# 2015-02-06_01-57-191.net
KiCad netlist of a schematic drawn in Altium Designer
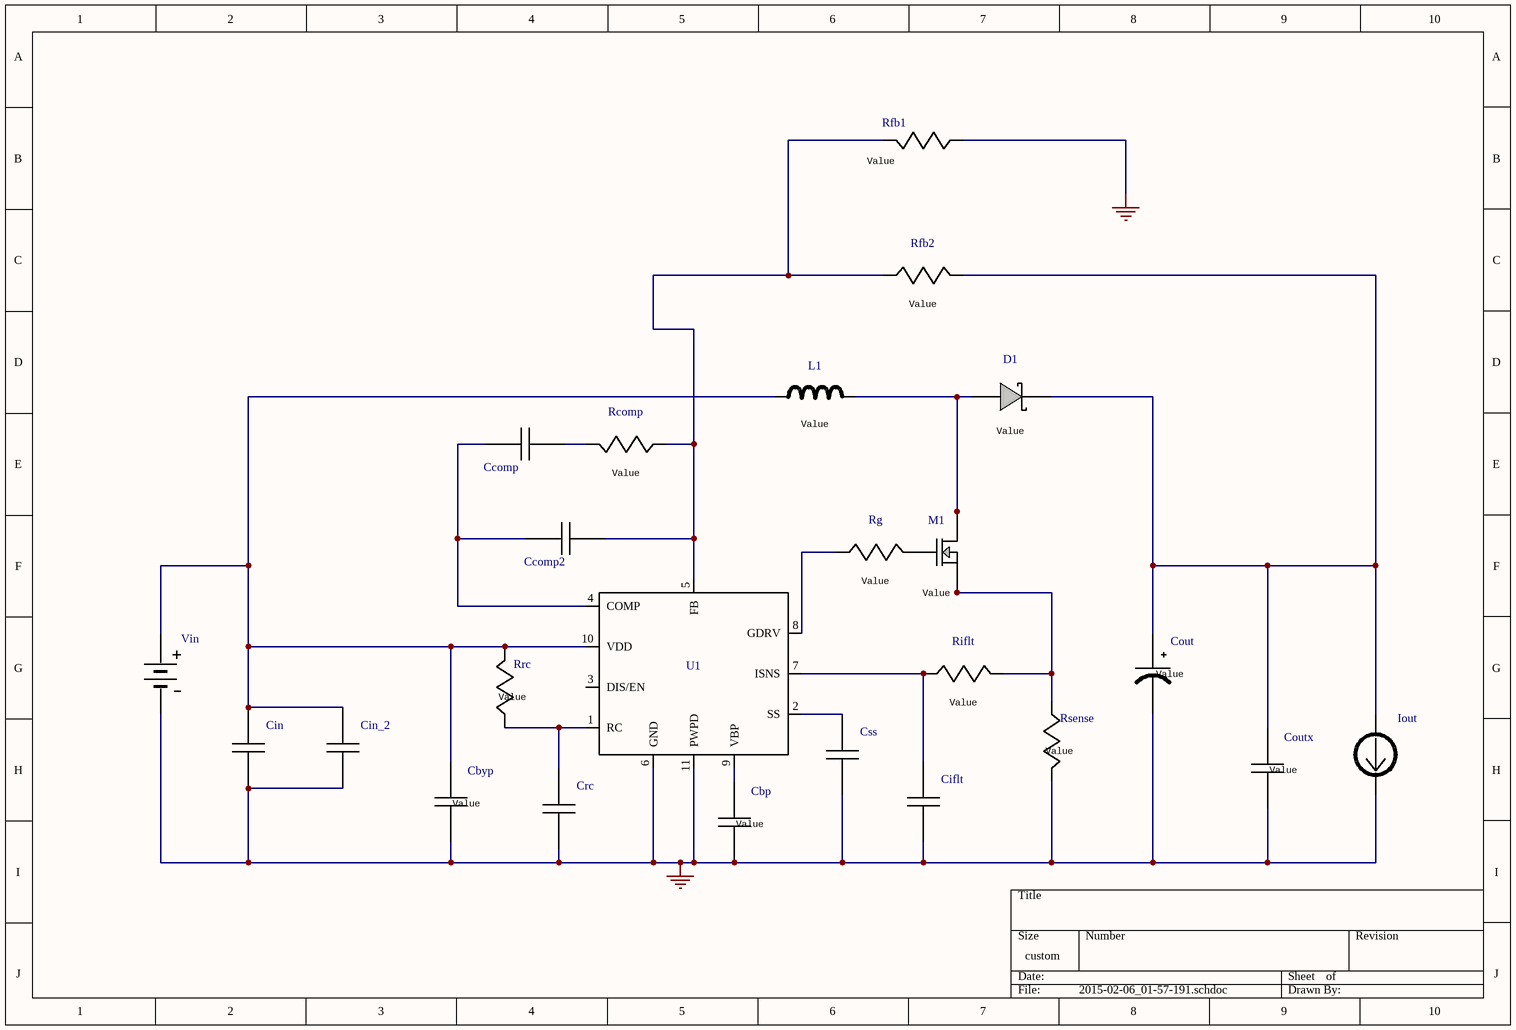
[diagram p0: 2015-02-06_01-57-191.schdoc]

(export (version "E")
  (design (tool "Eeschema 10.0.6"))
  (components
    (comp (ref "Cbp")
      (value "Value")
      (footprint "1608")
      (description "Imported")
      (fields (field (name "MANUFACTURER_PART_NUMBER") "C1608X5R1C105K"))
      (libsource (lib "TI WEBENCH") (part "C1608X5R1C105K"))
    )
    (comp (ref "Cbyp")
      (value "Value")
      (footprint "0805")
      (description "Imported")
      (fields (field (name "MANUFACTURER_PART_NUMBER") "EMK212B7474KD-T"))
      (libsource (lib "TI WEBENCH") (part "EMK212B7474KD-T"))
    )
    (comp (ref "Ccomp")
      (value "CC0805KRX7R9BB27")
      (footprint "0805")
      (description "Imported")
      (fields (field (name "MANUFACTURER_PART_NUMBER") "CC0805KRX7R9BB272"))
      (libsource (lib "TI WEBENCH") (part "CC0805KRX7R9BB27"))
    )
    (comp (ref "Ccomp2")
      (value "CC0805JRNPO9BN10")
      (footprint "0805")
      (description "Imported")
      (fields (field (name "MANUFACTURER_PART_NUMBER") "CC0805JRNPO9BN101"))
      (libsource (lib "TI WEBENCH") (part "CC0805JRNPO9BN10"))
    )
    (comp (ref "Ciflt")
      (value "CC0805JRNPO9BN15")
      (footprint "0805")
      (description "Imported")
      (fields (field (name "MANUFACTURER_PART_NUMBER") "CC0805JRNPO9BN151"))
      (libsource (lib "TI WEBENCH") (part "CC0805JRNPO9BN15"))
    )
    (comp (ref "Cin")
      (value "GRM21BR61E475MA1")
      (footprint "0805")
      (description "Imported")
      (fields (field (name "MANUFACTURER_PART_NUMBER") "GRM21BR61E475MA12L"))
      (libsource (lib "TI WEBENCH") (part "GRM21BR61E475MA1"))
    )
    (comp (ref "Cin_2")
      (value "GRM21BR61E475MA1")
      (footprint "0805")
      (description "Imported")
      (fields (field (name "MANUFACTURER_PART_NUMBER") "GRM21BR61E475MA12L"))
      (libsource (lib "TI WEBENCH") (part "GRM21BR61E475MA1"))
    )
    (comp (ref "Cout")
      (value "Value")
      (footprint "CAPSMT_62_E12")
      (description "Imported")
      (fields (field (name "MANUFACTURER_PART_NUMBER") "35SVPF82M"))
      (libsource (lib "TI WEBENCH") (part "35SVPF82M"))
    )
    (comp (ref "Coutx")
      (value "Value")
      (footprint "0805")
      (description "Imported")
      (fields (field (name "MANUFACTURER_PART_NUMBER") "GMK212B7105KG-T"))
      (libsource (lib "TI WEBENCH") (part "GMK212B7105KG-T"))
    )
    (comp (ref "Crc")
      (value "CC0805JRNPO9BN10")
      (footprint "0805")
      (description "Imported")
      (fields (field (name "MANUFACTURER_PART_NUMBER") "CC0805JRNPO9BN101"))
      (libsource (lib "TI WEBENCH") (part "CC0805JRNPO9BN10"))
    )
    (comp (ref "Css")
      (value "GRM155R61A683KA0")
      (footprint "0402")
      (description "Imported")
      (fields (field (name "MANUFACTURER_PART_NUMBER") "GRM155R61A683KA01D"))
      (libsource (lib "TI WEBENCH") (part "GRM155R61A683KA0"))
    )
    (comp (ref "D1")
      (value "Value")
      (footprint "SMA")
      (description "Imported")
      (fields (field (name "MANUFACTURER_PART_NUMBER") "B240A-13-F"))
      (libsource (lib "TI WEBENCH") (part "B240A-13-F"))
    )
    (comp (ref "Iout")
      (value "WB_CURRENT_LOAD")
      (description "Imported")
      (libsource (lib "TI WEBENCH") (part "WB_CURRENT_LOAD"))
    )
    (comp (ref "L1")
      (value "Value")
      (footprint "SRR1210")
      (description "Imported")
      (fields (field (name "MANUFACTURER_PART_NUMBER") "SRR1210-220M"))
      (libsource (lib "TI WEBENCH") (part "SRR1210-220M"))
    )
    (comp (ref "M1")
      (value "Value")
      (footprint "TRANS_NexFET_Q5A")
      (description "Imported")
      (fields (field (name "MANUFACTURER_PART_NUMBER") "CSD17551Q5A"))
      (libsource (lib "TI WEBENCH") (part "CSD17551Q5A"))
    )
    (comp (ref "Rcomp")
      (value "Value")
      (footprint "0402")
      (description "Imported")
      (fields (field (name "MANUFACTURER_PART_NUMBER") "CRCW040256K2FKED"))
      (libsource (lib "TI WEBENCH") (part "CRCW040256K2FKED"))
    )
    (comp (ref "Rfb1")
      (value "Value")
      (footprint "0402")
      (description "Imported")
      (fields (field (name "MANUFACTURER_PART_NUMBER") "CRCW04021K40FKED"))
      (libsource (lib "TI WEBENCH") (part "CRCW04021K40FKED"))
    )
    (comp (ref "Rfb2")
      (value "Value")
      (footprint "0805")
      (description "Imported")
      (fields (field (name "MANUFACTURER_PART_NUMBER") "RR1220P-473-D"))
      (libsource (lib "TI WEBENCH") (part "RR1220P-473-D"))
    )
    (comp (ref "Rg")
      (value "Value")
      (footprint "0402")
      (description "Imported")
      (fields (field (name "MANUFACTURER_PART_NUMBER") "CRCW040217R8FKED"))
      (libsource (lib "TI WEBENCH") (part "CRCW040217R8FKED"))
    )
    (comp (ref "Riflt")
      (value "Value")
      (footprint "0402")
      (description "Imported")
      (fields (field (name "MANUFACTURER_PART_NUMBER") "CRCW04021K00FKED"))
      (libsource (lib "TI WEBENCH") (part "CRCW04021K00FKED"))
    )
    (comp (ref "Rrc")
      (value "Value")
      (footprint "0402")
      (description "Imported")
      (fields (field (name "MANUFACTURER_PART_NUMBER") "CRCW0402316KFKED"))
      (libsource (lib "TI WEBENCH") (part "CRCW0402316KFKED"))
    )
    (comp (ref "Rsense")
      (value "Value")
      (footprint "1206")
      (description "Imported")
      (fields (field (name "MANUFACTURER_PART_NUMBER") "CSR1206FK25L0"))
      (libsource (lib "TI WEBENCH") (part "CSR1206FK25L0"))
    )
    (comp (ref "U1")
      (value "TPS40210DGQR")
      (footprint "S-PDSO-G10")
      (description "Imported")
      (libsource (lib "TI WEBENCH") (part "TPS40210DGQR"))
    )
    (comp (ref "Vin")
      (value "WB_BATTERY")
      (description "Imported")
      (libsource (lib "TI WEBENCH") (part "WB_BATTERY"))
    )
  )
  (nets
    (net (code "1") (name "0") (class "Default")
      (node (ref "Cbp") (pin "2") (pinfunction "2_2") (pintype "passive"))
      (node (ref "Cbyp") (pin "2") (pinfunction "2_2") (pintype "passive"))
      (node (ref "Ciflt") (pin "2") (pinfunction "2_2") (pintype "passive"))
      (node (ref "Cin") (pin "2") (pinfunction "2_2") (pintype "passive"))
      (node (ref "Cin_2") (pin "2") (pinfunction "2_2") (pintype "passive"))
      (node (ref "Cout") (pin "2") (pinfunction "-_2") (pintype "passive"))
      (node (ref "Coutx") (pin "2") (pinfunction "2_2") (pintype "passive"))
      (node (ref "Crc") (pin "2") (pinfunction "2_2") (pintype "passive"))
      (node (ref "Css") (pin "2") (pinfunction "2_2") (pintype "passive"))
      (node (ref "Iout") (pin "2") (pinfunction "-_2") (pintype "passive"))
      (node (ref "Rfb1") (pin "2") (pinfunction "2_2") (pintype "passive"))
      (node (ref "Rsense") (pin "1") (pinfunction "1_1") (pintype "passive"))
      (node (ref "U1") (pin "11") (pinfunction "PWPD_11") (pintype "passive"))
      (node (ref "U1") (pin "6") (pinfunction "GND_6") (pintype "passive"))
      (node (ref "Vin") (pin "2") (pinfunction "-_2") (pintype "passive"))
    )
    (net (code "2") (name "Net-(Ccomp-Pad2)") (class "Default")
      (node (ref "Ccomp") (pin "2") (pinfunction "2_2") (pintype "passive"))
      (node (ref "Rcomp") (pin "1") (pinfunction "1_1") (pintype "passive"))
    )
    (net (code "3") (name "Net-(Cout-+)") (class "Default")
      (node (ref "Cout") (pin "1") (pinfunction "+_1") (pintype "passive"))
      (node (ref "Coutx") (pin "1") (pinfunction "1_1") (pintype "passive"))
      (node (ref "D1") (pin "1") (pinfunction "K_1") (pintype "passive"))
      (node (ref "Iout") (pin "1") (pinfunction "+_1") (pintype "passive"))
      (node (ref "Rfb2") (pin "1") (pinfunction "1_1") (pintype "passive"))
    )
    (net (code "4") (name "Net-(D1-A)") (class "Default")
      (node (ref "D1") (pin "2") (pinfunction "A_2") (pintype "passive"))
      (node (ref "L1") (pin "2") (pinfunction "2_2") (pintype "passive"))
      (node (ref "M1") (pin "5") (pinfunction "Drain_5") (pintype "passive"))
      (node (ref "M1") (pin "6") (pinfunction "Drain_6") (pintype "passive"))
      (node (ref "M1") (pin "7") (pinfunction "Drain_7") (pintype "passive"))
      (node (ref "M1") (pin "8") (pinfunction "Drain_8") (pintype "passive"))
      (node (ref "M1") (pin "9") (pinfunction "Drain_9") (pintype "passive"))
    )
    (net (code "5") (name "Net-(M1-Gate)") (class "Default")
      (node (ref "M1") (pin "4") (pinfunction "Gate_4") (pintype "passive"))
      (node (ref "Rg") (pin "1") (pinfunction "1_1") (pintype "passive"))
    )
    (net (code "6") (name "Net-(M1-Source-Pad1)") (class "Default")
      (node (ref "M1") (pin "1") (pinfunction "Source_1") (pintype "passive"))
      (node (ref "M1") (pin "2") (pinfunction "Source_2") (pintype "passive"))
      (node (ref "M1") (pin "3") (pinfunction "Source_3") (pintype "passive"))
      (node (ref "Riflt") (pin "1") (pinfunction "1_1") (pintype "passive"))
      (node (ref "Rsense") (pin "2") (pinfunction "2_2") (pintype "passive"))
    )
    (net (code "7") (name "Net-(U1-COMP)") (class "Default")
      (node (ref "Ccomp") (pin "1") (pinfunction "1_1") (pintype "passive"))
      (node (ref "Ccomp2") (pin "1") (pinfunction "1_1") (pintype "passive"))
      (node (ref "U1") (pin "4") (pinfunction "COMP_4") (pintype "passive"))
    )
    (net (code "8") (name "Net-(U1-FB)") (class "Default")
      (node (ref "Ccomp2") (pin "2") (pinfunction "2_2") (pintype "passive"))
      (node (ref "Rcomp") (pin "2") (pinfunction "2_2") (pintype "passive"))
      (node (ref "Rfb1") (pin "1") (pinfunction "1_1") (pintype "passive"))
      (node (ref "Rfb2") (pin "2") (pinfunction "2_2") (pintype "passive"))
      (node (ref "U1") (pin "5") (pinfunction "FB_5") (pintype "passive"))
    )
    (net (code "9") (name "Net-(U1-GDRV)") (class "Default")
      (node (ref "Rg") (pin "2") (pinfunction "2_2") (pintype "passive"))
      (node (ref "U1") (pin "8") (pinfunction "GDRV_8") (pintype "passive"))
    )
    (net (code "10") (name "Net-(U1-ISNS)") (class "Default")
      (node (ref "Ciflt") (pin "1") (pinfunction "1_1") (pintype "passive"))
      (node (ref "Riflt") (pin "2") (pinfunction "2_2") (pintype "passive"))
      (node (ref "U1") (pin "7") (pinfunction "ISNS_7") (pintype "passive"))
    )
    (net (code "11") (name "Net-(U1-RC)") (class "Default")
      (node (ref "Crc") (pin "1") (pinfunction "1_1") (pintype "passive"))
      (node (ref "Rrc") (pin "2") (pinfunction "2_2") (pintype "passive"))
      (node (ref "U1") (pin "1") (pinfunction "RC_1") (pintype "passive"))
    )
    (net (code "12") (name "Net-(U1-SS)") (class "Default")
      (node (ref "Css") (pin "1") (pinfunction "1_1") (pintype "passive"))
      (node (ref "U1") (pin "2") (pinfunction "SS_2") (pintype "passive"))
    )
    (net (code "13") (name "Net-(U1-VBP)") (class "Default")
      (node (ref "Cbp") (pin "1") (pinfunction "1_1") (pintype "passive"))
      (node (ref "U1") (pin "9") (pinfunction "VBP_9") (pintype "passive"))
    )
    (net (code "14") (name "Net-(U1-VDD)") (class "Default")
      (node (ref "Cbyp") (pin "1") (pinfunction "1_1") (pintype "passive"))
      (node (ref "Cin") (pin "1") (pinfunction "1_1") (pintype "passive"))
      (node (ref "Cin_2") (pin "1") (pinfunction "1_1") (pintype "passive"))
      (node (ref "L1") (pin "1") (pinfunction "1_1") (pintype "passive"))
      (node (ref "Rrc") (pin "1") (pinfunction "1_1") (pintype "passive"))
      (node (ref "U1") (pin "10") (pinfunction "VDD_10") (pintype "passive"))
      (node (ref "Vin") (pin "1") (pinfunction "+_1") (pintype "passive"))
    )
    (net (code "15") (name "unconnected-(U1-DIS{slash}EN-Pad3)") (class "Default")
      (node (ref "U1") (pin "3") (pinfunction "DIS/EN_3") (pintype "passive"))
    )
  )
)
